# design.net
KiCad netlist of a schematic drawn in EasyEDA
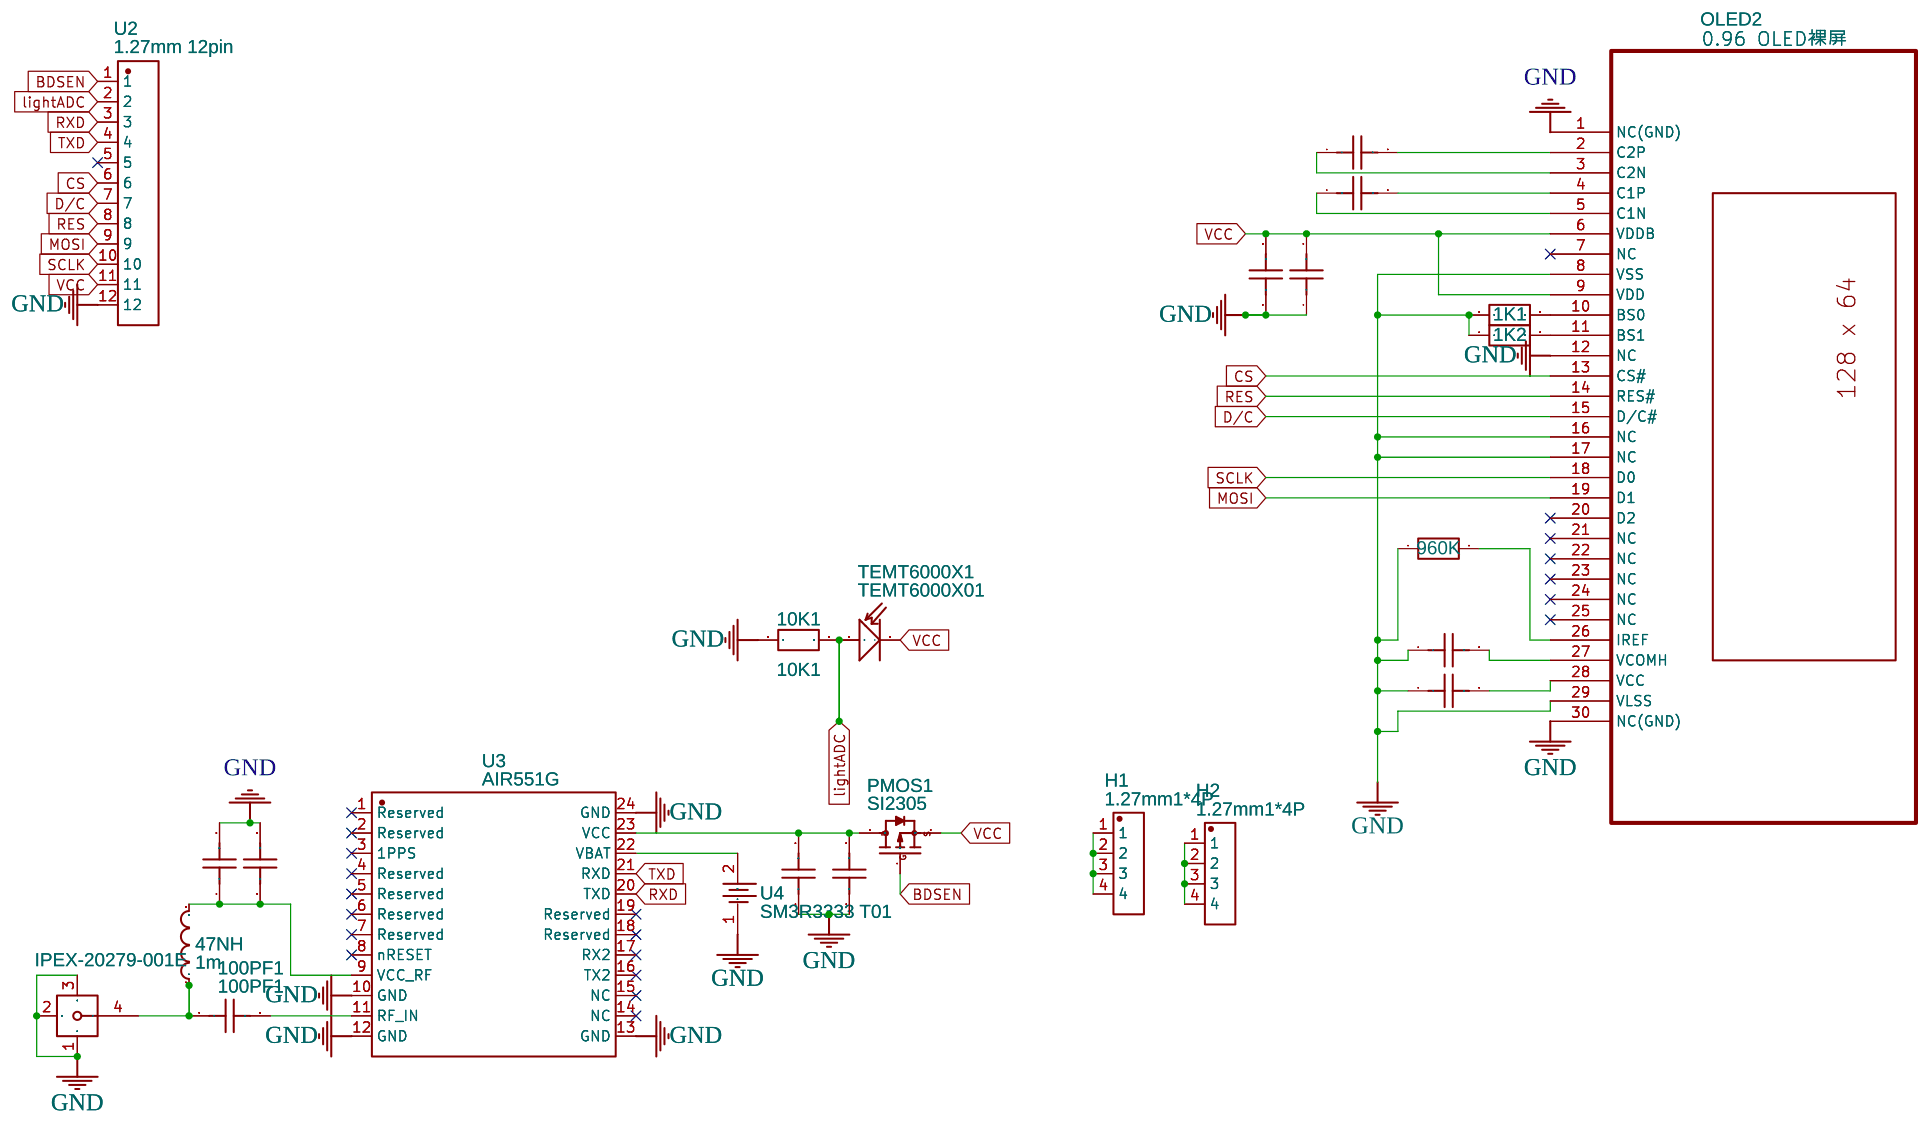
[diagram p0: schematic sheet]

(export (version "E")
  (design (tool "Eeschema 10.0.6"))
  (components
    (comp (ref "1K1") (value "1k") (libsource (lib "") (part "R_0603_EU")))
    (comp (ref "1K2") (value "1k") (libsource (lib "") (part "R_0603_EU")))
    (comp (ref "1U3") (value "1U") (libsource (lib "") (part "C_0603_US_3")))
    (comp (ref "1U4") (value "1u") (libsource (lib "") (part "C_0603_US_3")))
    (comp (ref "1U5") (value "1u") (libsource (lib "") (part "C_0603_US_1")))
    (comp (ref "1U6") (value "1U") (libsource (lib "") (part "C_0603_US_1")))
    (comp (ref "2.1UF") (value "0.1u") (libsource (lib "") (part "C_0603_US_7")))
    (comp (ref "2.2UF") (value "0.1u") (libsource (lib "") (part "C_0603_US_5")))
    (comp (ref "2.3UF") (value "0.1u") (libsource (lib "") (part "C_0603_US_2")))
    (comp (ref "4.7U1") (value "0.1u") (libsource (lib "") (part "C_0603_US_6")))
    (comp (ref "4.7U2") (value "0.1u") (libsource (lib "") (part "C_0603_US_4")))
    (comp (ref "4.7U3") (value "0.1u") (libsource (lib "") (part "C_0603_US_6")))
    (comp (ref "10K1") (value "10K1") (libsource (lib "") (part "R_0603_EU_2")))
    (comp (ref "47NH") (value "1m") (libsource (lib "") (part "L0603_US")))
    (comp (ref "100PF1") (value "100PF1") (libsource (lib "") (part "C_0603_US")))
    (comp (ref "960K") (value "1k") (libsource (lib "") (part "R_0603_EU_1")))
    (comp (ref "H1")
      (value "1.27mm1*4P")
      (fields
        (field (name "BOM_Manufacturer Part") "1.27mm1*12P Straight Headers  Pins")
        (field (name "BOM_Supplier Part") "C28953")
      )
      (libsource (lib "") (part "1.27mm1*4P"))
    )
    (comp (ref "H2")
      (value "1.27mm1*4P")
      (fields
        (field (name "BOM_Manufacturer Part") "1.27mm1*12P Straight Headers  Pins")
        (field (name "BOM_Supplier Part") "C28953")
      )
      (libsource (lib "") (part "1.27mm1*4P"))
    )
    (comp (ref "NO")
      (value "IPEX-20279-001E")
      (fields (field (name "BOM_Supplier Part") "C9900004475"))
      (libsource (lib "") (part "IPEX-20279-001E"))
    )
    (comp (ref "OLED2")
      (value "0.96 OLED裸屏")
      (fields (field (name "BOM_Manufacturer Part") "SSD1315-OLED-12864-0.96"))
      (libsource (lib "") (part "0.96 OLED裸屏"))
    )
    (comp (ref "PMOS1")
      (value "SI2305")
      (fields (field (name "BOM_Supplier Part") "C181088"))
      (libsource (lib "") (part "SI2305"))
    )
    (comp (ref "TEMT6000X1")
      (value "TEMT6000X01")
      (fields (field (name "BOM_Supplier Part") "C94098"))
      (libsource (lib "") (part "TEMT6000X01"))
    )
    (comp (ref "U2") (value "1.27mm 12pin") (libsource (lib "") (part "1.27mm 12pin")))
    (comp (ref "U3")
      (value "AIR551G")
      (fields
        (field (name "BOM_Manufacturer Part") "Air551G")
        (field (name "BOM_Supplier Part") "C9900011816")
      )
      (libsource (lib "") (part "AIR551G"))
    )
    (comp (ref "U4")
      (value "SM3R3333 T01")
      (fields (field (name "BOM_Supplier Part") "C260765"))
      (libsource (lib "") (part "SM3R3333 T01"))
    )
  )
  (nets
    (net (code "1") (name "BDSEN") (class "Default")
      (node (ref "PMOS1") (pin "1") (pinfunction "G_1") (pintype "unspecified"))
      (node (ref "U2") (pin "1") (pinfunction "1_1") (pintype "unspecified"))
    )
    (net (code "2") (name "CS") (class "Default")
      (node (ref "OLED2") (pin "13") (pinfunction "CS#_13") (pintype "passive"))
      (node (ref "U2") (pin "6") (pinfunction "6_6") (pintype "unspecified"))
    )
    (net (code "3") (name "D{slash}C") (class "Default")
      (node (ref "OLED2") (pin "15") (pinfunction "D/C#_15") (pintype "passive"))
      (node (ref "U2") (pin "7") (pinfunction "7_7") (pintype "unspecified"))
    )
    (net (code "4") (name "GND") (class "Default")
      (node (ref "10K1") (pin "1") (pinfunction "1_1") (pintype "unspecified"))
      (node (ref "1K1") (pin "1") (pinfunction "1_1") (pintype "unspecified"))
      (node (ref "1K2") (pin "1") (pinfunction "1_1") (pintype "unspecified"))
      (node (ref "1U5") (pin "1") (pinfunction "1_1") (pintype "unspecified"))
      (node (ref "1U6") (pin "1") (pinfunction "1_1") (pintype "unspecified"))
      (node (ref "2.1UF") (pin "2") (pinfunction "2_2") (pintype "unspecified"))
      (node (ref "2.2UF") (pin "1") (pinfunction "1_1") (pintype "unspecified"))
      (node (ref "2.3UF") (pin "1") (pinfunction "1_1") (pintype "unspecified"))
      (node (ref "4.7U1") (pin "2") (pinfunction "2_2") (pintype "unspecified"))
      (node (ref "4.7U2") (pin "1") (pinfunction "1_1") (pintype "unspecified"))
      (node (ref "4.7U3") (pin "1") (pinfunction "1_1") (pintype "unspecified"))
      (node (ref "960K") (pin "1") (pinfunction "1_1") (pintype "unspecified"))
      (node (ref "NO") (pin "1") (pinfunction "1_1") (pintype "unspecified"))
      (node (ref "NO") (pin "2") (pinfunction "2_2") (pintype "unspecified"))
      (node (ref "NO") (pin "3") (pinfunction "3_3") (pintype "unspecified"))
      (node (ref "OLED2") (pin "1") (pinfunction "NC(GND)_1") (pintype "passive"))
      (node (ref "OLED2") (pin "12") (pinfunction "NC_12") (pintype "passive"))
      (node (ref "OLED2") (pin "16") (pinfunction "NC_16") (pintype "passive"))
      (node (ref "OLED2") (pin "17") (pinfunction "NC_17") (pintype "passive"))
      (node (ref "OLED2") (pin "29") (pinfunction "VLSS_29") (pintype "passive"))
      (node (ref "OLED2") (pin "30") (pinfunction "NC(GND)_30") (pintype "passive"))
      (node (ref "OLED2") (pin "8") (pinfunction "VSS_8") (pintype "passive"))
      (node (ref "U2") (pin "12") (pinfunction "12_12") (pintype "unspecified"))
      (node (ref "U3") (pin "10") (pinfunction "GND_10") (pintype "unspecified"))
      (node (ref "U3") (pin "12") (pinfunction "GND_12") (pintype "unspecified"))
      (node (ref "U3") (pin "13") (pinfunction "GND_13") (pintype "unspecified"))
      (node (ref "U3") (pin "24") (pinfunction "GND_24") (pintype "unspecified"))
      (node (ref "U4") (pin "1") (pinfunction "1_1") (pintype "input"))
    )
    (net (code "5") (name "MOSI") (class "Default")
      (node (ref "OLED2") (pin "19") (pinfunction "D1_19") (pintype "passive"))
      (node (ref "U2") (pin "9") (pinfunction "9_9") (pintype "unspecified"))
    )
    (net (code "6") (name "Net-(100PF1-Pad1)") (class "Default")
      (node (ref "100PF1") (pin "1") (pinfunction "1_1") (pintype "unspecified"))
      (node (ref "47NH") (pin "1") (pinfunction "1_1") (pintype "unspecified"))
      (node (ref "NO") (pin "4") (pinfunction "4_4") (pintype "unspecified"))
    )
    (net (code "7") (name "Net-(H1-Pad1)") (class "Default")
      (node (ref "H1") (pin "1") (pinfunction "1_1") (pintype "unspecified"))
      (node (ref "H1") (pin "2") (pinfunction "2_2") (pintype "unspecified"))
      (node (ref "H1") (pin "3") (pinfunction "3_3") (pintype "unspecified"))
      (node (ref "H1") (pin "4") (pinfunction "4_4") (pintype "unspecified"))
    )
    (net (code "8") (name "Net-(H2-Pad1)") (class "Default")
      (node (ref "H2") (pin "1") (pinfunction "1_1") (pintype "unspecified"))
      (node (ref "H2") (pin "2") (pinfunction "2_2") (pintype "unspecified"))
      (node (ref "H2") (pin "3") (pinfunction "3_3") (pintype "unspecified"))
      (node (ref "H2") (pin "4") (pinfunction "4_4") (pintype "unspecified"))
    )
    (net (code "9") (name "Net-(OLED2-BS0)") (class "Default")
      (node (ref "1K1") (pin "2") (pinfunction "2_2") (pintype "unspecified"))
      (node (ref "OLED2") (pin "10") (pinfunction "BS0_10") (pintype "passive"))
    )
    (net (code "10") (name "Net-(OLED2-BS1)") (class "Default")
      (node (ref "1K2") (pin "2") (pinfunction "2_2") (pintype "unspecified"))
      (node (ref "OLED2") (pin "11") (pinfunction "BS1_11") (pintype "passive"))
    )
    (net (code "11") (name "Net-(OLED2-C1N)") (class "Default")
      (node (ref "1U3") (pin "1") (pinfunction "1_1") (pintype "unspecified"))
      (node (ref "OLED2") (pin "5") (pinfunction "C1N_5") (pintype "passive"))
    )
    (net (code "12") (name "Net-(OLED2-C1P)") (class "Default")
      (node (ref "1U3") (pin "2") (pinfunction "2_2") (pintype "unspecified"))
      (node (ref "OLED2") (pin "4") (pinfunction "C1P_4") (pintype "passive"))
    )
    (net (code "13") (name "Net-(OLED2-C2N)") (class "Default")
      (node (ref "1U4") (pin "1") (pinfunction "1_1") (pintype "unspecified"))
      (node (ref "OLED2") (pin "3") (pinfunction "C2N_3") (pintype "passive"))
    )
    (net (code "14") (name "Net-(OLED2-C2P)") (class "Default")
      (node (ref "1U4") (pin "2") (pinfunction "2_2") (pintype "unspecified"))
      (node (ref "OLED2") (pin "2") (pinfunction "C2P_2") (pintype "passive"))
    )
    (net (code "15") (name "Net-(OLED2-IREF)") (class "Default")
      (node (ref "960K") (pin "2") (pinfunction "2_2") (pintype "unspecified"))
      (node (ref "OLED2") (pin "26") (pinfunction "IREF_26") (pintype "passive"))
    )
    (net (code "16") (name "Net-(OLED2-VCC)") (class "Default")
      (node (ref "2.2UF") (pin "2") (pinfunction "2_2") (pintype "unspecified"))
      (node (ref "OLED2") (pin "28") (pinfunction "VCC_28") (pintype "passive"))
    )
    (net (code "17") (name "Net-(OLED2-VCOMH)") (class "Default")
      (node (ref "4.7U2") (pin "2") (pinfunction "2_2") (pintype "unspecified"))
      (node (ref "OLED2") (pin "27") (pinfunction "VCOMH_27") (pintype "passive"))
    )
    (net (code "18") (name "Net-(PMOS1-D)") (class "Default")
      (node (ref "2.3UF") (pin "2") (pinfunction "2_2") (pintype "unspecified"))
      (node (ref "4.7U3") (pin "2") (pinfunction "2_2") (pintype "unspecified"))
      (node (ref "PMOS1") (pin "3") (pinfunction "D_3") (pintype "unspecified"))
      (node (ref "U3") (pin "23") (pinfunction "VCC_23") (pintype "unspecified"))
    )
    (net (code "19") (name "Net-(U3-RF_IN)") (class "Default")
      (node (ref "100PF1") (pin "2") (pinfunction "2_2") (pintype "unspecified"))
      (node (ref "U3") (pin "11") (pinfunction "RF_IN_11") (pintype "unspecified"))
    )
    (net (code "20") (name "Net-(U3-VBAT)") (class "Default")
      (node (ref "U3") (pin "22") (pinfunction "VBAT_22") (pintype "unspecified"))
      (node (ref "U4") (pin "2") (pinfunction "2_2") (pintype "input"))
    )
    (net (code "21") (name "Net-(U3-VCC_RF)") (class "Default")
      (node (ref "2.1UF") (pin "1") (pinfunction "1_1") (pintype "unspecified"))
      (node (ref "4.7U1") (pin "1") (pinfunction "1_1") (pintype "unspecified"))
      (node (ref "47NH") (pin "2") (pinfunction "2_2") (pintype "unspecified"))
      (node (ref "U3") (pin "9") (pinfunction "VCC_RF_9") (pintype "unspecified"))
    )
    (net (code "22") (name "RES") (class "Default")
      (node (ref "OLED2") (pin "14") (pinfunction "RES#_14") (pintype "passive"))
      (node (ref "U2") (pin "8") (pinfunction "8_8") (pintype "unspecified"))
    )
    (net (code "23") (name "RXD") (class "Default")
      (node (ref "U2") (pin "3") (pinfunction "3_3") (pintype "unspecified"))
      (node (ref "U3") (pin "20") (pinfunction "TXD_20") (pintype "unspecified"))
    )
    (net (code "24") (name "SCLK") (class "Default")
      (node (ref "OLED2") (pin "18") (pinfunction "D0_18") (pintype "passive"))
      (node (ref "U2") (pin "10") (pinfunction "10_10") (pintype "unspecified"))
    )
    (net (code "25") (name "TXD") (class "Default")
      (node (ref "U2") (pin "4") (pinfunction "4_4") (pintype "unspecified"))
      (node (ref "U3") (pin "21") (pinfunction "RXD_21") (pintype "unspecified"))
    )
    (net (code "26") (name "VCC") (class "Default")
      (node (ref "1U5") (pin "2") (pinfunction "2_2") (pintype "unspecified"))
      (node (ref "1U6") (pin "2") (pinfunction "2_2") (pintype "unspecified"))
      (node (ref "OLED2") (pin "6") (pinfunction "VDDB_6") (pintype "passive"))
      (node (ref "OLED2") (pin "9") (pinfunction "VDD_9") (pintype "passive"))
      (node (ref "PMOS1") (pin "2") (pinfunction "S_2") (pintype "unspecified"))
      (node (ref "TEMT6000X1") (pin "3") (pinfunction "-_3") (pintype "unspecified"))
      (node (ref "U2") (pin "11") (pinfunction "11_11") (pintype "unspecified"))
    )
    (net (code "27") (name "lightADC") (class "Default")
      (node (ref "10K1") (pin "2") (pinfunction "2_2") (pintype "unspecified"))
      (node (ref "TEMT6000X1") (pin "1") (pinfunction "+_1") (pintype "unspecified"))
      (node (ref "TEMT6000X1") (pin "2") (pinfunction "+_2") (pintype "unspecified"))
      (node (ref "U2") (pin "2") (pinfunction "2_2") (pintype "unspecified"))
    )
    (net (code "28") (name "unconnected-(OLED2-D2-Pad20)") (class "Default")
      (node (ref "OLED2") (pin "20") (pinfunction "D2_20") (pintype "passive+no_connect"))
    )
    (net (code "29") (name "unconnected-(OLED2-NC-Pad7)") (class "Default")
      (node (ref "OLED2") (pin "7") (pinfunction "NC_7") (pintype "passive+no_connect"))
    )
    (net (code "30") (name "unconnected-(OLED2-NC-Pad21)") (class "Default")
      (node (ref "OLED2") (pin "21") (pinfunction "NC_21") (pintype "passive+no_connect"))
    )
    (net (code "31") (name "unconnected-(OLED2-NC-Pad22)") (class "Default")
      (node (ref "OLED2") (pin "22") (pinfunction "NC_22") (pintype "passive+no_connect"))
    )
    (net (code "32") (name "unconnected-(OLED2-NC-Pad23)") (class "Default")
      (node (ref "OLED2") (pin "23") (pinfunction "NC_23") (pintype "passive+no_connect"))
    )
    (net (code "33") (name "unconnected-(OLED2-NC-Pad24)") (class "Default")
      (node (ref "OLED2") (pin "24") (pinfunction "NC_24") (pintype "passive+no_connect"))
    )
    (net (code "34") (name "unconnected-(OLED2-NC-Pad25)") (class "Default")
      (node (ref "OLED2") (pin "25") (pinfunction "NC_25") (pintype "passive+no_connect"))
    )
    (net (code "35") (name "unconnected-(U2-Pad5)") (class "Default")
      (node (ref "U2") (pin "5") (pinfunction "5_5") (pintype "unspecified+no_connect"))
    )
    (net (code "36") (name "unconnected-(U3-1PPS-Pad3)") (class "Default")
      (node (ref "U3") (pin "3") (pinfunction "1PPS_3") (pintype "unspecified+no_connect"))
    )
    (net (code "37") (name "unconnected-(U3-NC-Pad14)") (class "Default")
      (node (ref "U3") (pin "14") (pinfunction "NC_14") (pintype "unspecified+no_connect"))
    )
    (net (code "38") (name "unconnected-(U3-NC-Pad15)") (class "Default")
      (node (ref "U3") (pin "15") (pinfunction "NC_15") (pintype "unspecified+no_connect"))
    )
    (net (code "39") (name "unconnected-(U3-RX2-Pad17)") (class "Default")
      (node (ref "U3") (pin "17") (pinfunction "RX2_17") (pintype "unspecified+no_connect"))
    )
    (net (code "40") (name "unconnected-(U3-Reserved-Pad1)") (class "Default")
      (node (ref "U3") (pin "1") (pinfunction "Reserved_1") (pintype "unspecified+no_connect"))
    )
    (net (code "41") (name "unconnected-(U3-Reserved-Pad2)") (class "Default")
      (node (ref "U3") (pin "2") (pinfunction "Reserved_2") (pintype "unspecified+no_connect"))
    )
    (net (code "42") (name "unconnected-(U3-Reserved-Pad4)") (class "Default")
      (node (ref "U3") (pin "4") (pinfunction "Reserved_4") (pintype "unspecified+no_connect"))
    )
    (net (code "43") (name "unconnected-(U3-Reserved-Pad5)") (class "Default")
      (node (ref "U3") (pin "5") (pinfunction "Reserved_5") (pintype "unspecified+no_connect"))
    )
    (net (code "44") (name "unconnected-(U3-Reserved-Pad6)") (class "Default")
      (node (ref "U3") (pin "6") (pinfunction "Reserved_6") (pintype "unspecified+no_connect"))
    )
    (net (code "45") (name "unconnected-(U3-Reserved-Pad7)") (class "Default")
      (node (ref "U3") (pin "7") (pinfunction "Reserved_7") (pintype "unspecified+no_connect"))
    )
    (net (code "46") (name "unconnected-(U3-Reserved-Pad18)") (class "Default")
      (node (ref "U3") (pin "18") (pinfunction "Reserved_18") (pintype "unspecified+no_connect"))
    )
    (net (code "47") (name "unconnected-(U3-Reserved-Pad19)") (class "Default")
      (node (ref "U3") (pin "19") (pinfunction "Reserved_19") (pintype "unspecified+no_connect"))
    )
    (net (code "48") (name "unconnected-(U3-TX2-Pad16)") (class "Default")
      (node (ref "U3") (pin "16") (pinfunction "TX2_16") (pintype "unspecified+no_connect"))
    )
    (net (code "49") (name "unconnected-(U3-nRESET-Pad8)") (class "Default")
      (node (ref "U3") (pin "8") (pinfunction "nRESET_8") (pintype "unspecified+no_connect"))
    )
  )
)
